# sparkpunk_sequencer.net
KiCad netlist of a schematic drawn in EAGLE
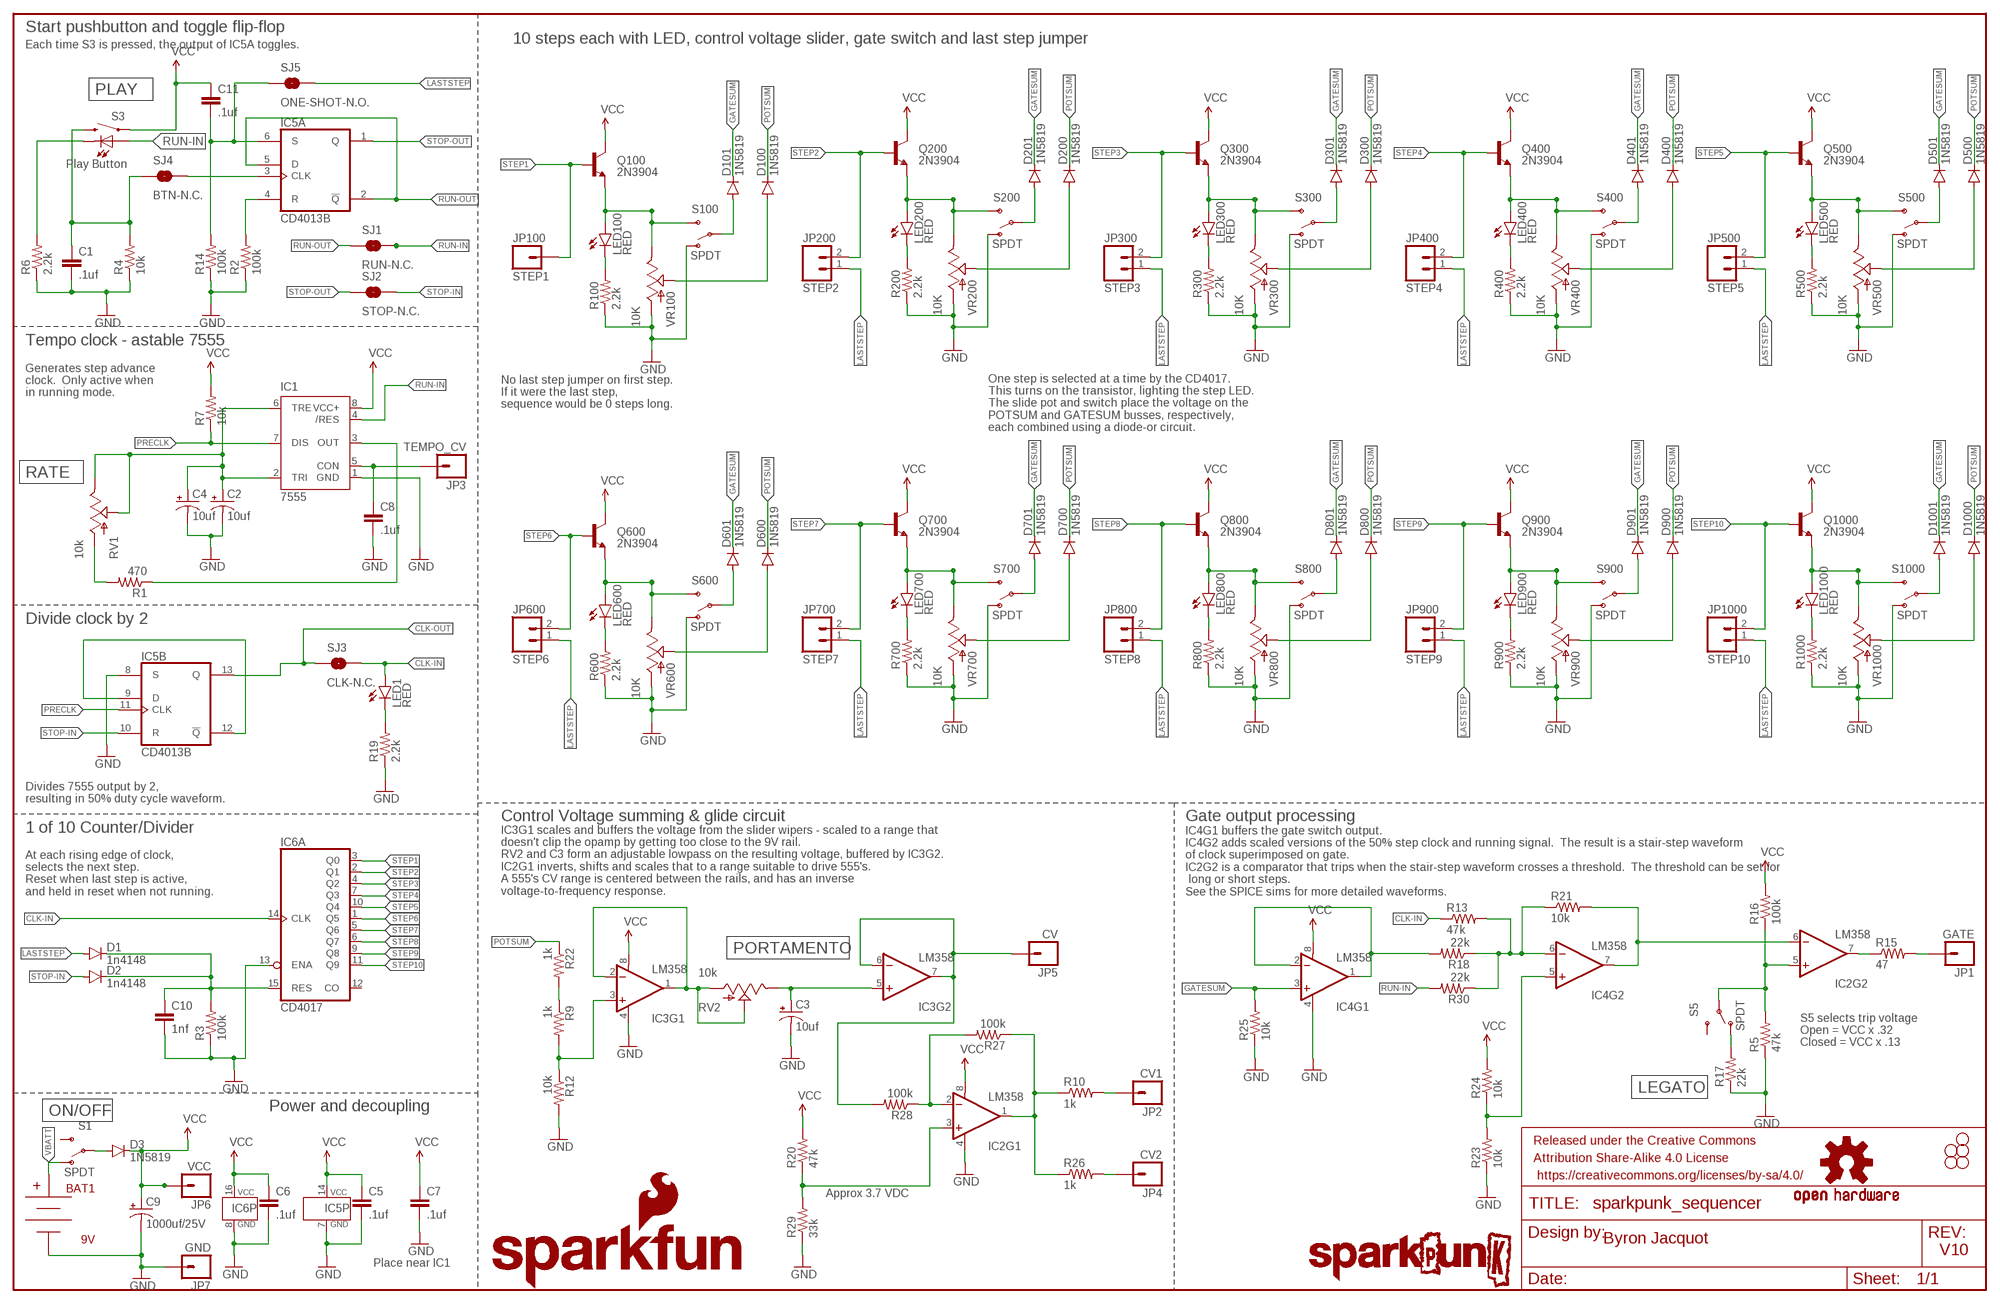
[diagram p0: schematic, sheet 1]

(export (version "E")
  (design (tool "Eeschema 10.0.6"))
  (components
    (comp (ref "BAT1")
      (value "9V")
      (footprint "eagle-import:BC9VPC_KIT")
      (libsource (lib "eagle-import") (part "BC9VPCKIT_SOLDERMASK"))
    )
    (comp (ref "C1")
      (value ".1uf")
      (footprint "eagle-import:CAP-PTH-SMALL-KIT")
      (libsource (lib "eagle-import") (part "0.1UF-50V-20%(PTH)KIT-EZ"))
    )
    (comp (ref "C2")
      (value "10uf")
      (footprint "eagle-import:CPOL-RADIAL-10UF-25V-KIT")
      (libsource (lib "eagle-import") (part "10UF-25V-20%(PTH)KIT"))
    )
    (comp (ref "C3")
      (value "10uf")
      (footprint "eagle-import:CPOL-RADIAL-10UF-25V-KIT")
      (libsource (lib "eagle-import") (part "10UF-25V-20%(PTH)KIT"))
    )
    (comp (ref "C4")
      (value "10uf")
      (footprint "eagle-import:CPOL-RADIAL-10UF-25V-KIT")
      (libsource (lib "eagle-import") (part "10UF-25V-20%(PTH)KIT"))
    )
    (comp (ref "C5")
      (value ".1uf")
      (footprint "eagle-import:CAP-PTH-SMALL-KIT")
      (libsource (lib "eagle-import") (part "0.1UF-50V-20%(PTH)KIT-EZ"))
    )
    (comp (ref "C6")
      (value ".1uf")
      (footprint "eagle-import:CAP-PTH-SMALL-KIT")
      (libsource (lib "eagle-import") (part "0.1UF-50V-20%(PTH)KIT-EZ"))
    )
    (comp (ref "C7")
      (value ".1uf")
      (footprint "eagle-import:CAP-PTH-SMALL-KIT")
      (libsource (lib "eagle-import") (part "0.1UF-50V-20%(PTH)KIT-EZ"))
    )
    (comp (ref "C8")
      (value ".1uf")
      (footprint "eagle-import:CAP-PTH-SMALL-KIT")
      (libsource (lib "eagle-import") (part "0.1UF-50V-20%(PTH)KIT-EZ"))
    )
    (comp (ref "C9")
      (value "1000uf/25V")
      (footprint "eagle-import:CPOL-RADIAL-1000UF-25V-KIT")
      (libsource (lib "eagle-import") (part "1000UF-25V(PTH)KIT"))
    )
    (comp (ref "C10")
      (value "1nf")
      (footprint "eagle-import:CAP-PTH-SMALL-KIT")
      (libsource (lib "eagle-import") (part "CAPKIT"))
    )
    (comp (ref "C11")
      (value ".1uf")
      (footprint "eagle-import:CAP-PTH-SMALL-KIT")
      (libsource (lib "eagle-import") (part "0.1UF-50V-20%(PTH)KIT-EZ"))
    )
    (comp (ref "D1")
      (value "1n4148")
      (footprint "eagle-import:DIODE-1N4148-KIT")
      (libsource (lib "eagle-import") (part "DIODEKIT"))
    )
    (comp (ref "D2")
      (value "1n4148")
      (footprint "eagle-import:DIODE-1N4148-KIT")
      (libsource (lib "eagle-import") (part "DIODEKIT"))
    )
    (comp (ref "D3")
      (value "1N5819")
      (footprint "eagle-import:DIODE-1N4001-KIT")
      (libsource (lib "eagle-import") (part "DIODE"))
    )
    (comp (ref "D100")
      (value "1N5819")
      (footprint "eagle-import:DIODE-1N4001-KIT")
      (libsource (lib "eagle-import") (part "DIODE"))
    )
    (comp (ref "D101")
      (value "1N5819")
      (footprint "eagle-import:DIODE-1N4001-KIT")
      (libsource (lib "eagle-import") (part "DIODE"))
    )
    (comp (ref "D200")
      (value "1N5819")
      (footprint "eagle-import:DIODE-1N4001-KIT")
      (libsource (lib "eagle-import") (part "DIODE"))
    )
    (comp (ref "D201")
      (value "1N5819")
      (footprint "eagle-import:DIODE-1N4001-KIT")
      (libsource (lib "eagle-import") (part "DIODE"))
    )
    (comp (ref "D300")
      (value "1N5819")
      (footprint "eagle-import:DIODE-1N4001-KIT")
      (libsource (lib "eagle-import") (part "DIODE"))
    )
    (comp (ref "D301")
      (value "1N5819")
      (footprint "eagle-import:DIODE-1N4001-KIT")
      (libsource (lib "eagle-import") (part "DIODE"))
    )
    (comp (ref "D400")
      (value "1N5819")
      (footprint "eagle-import:DIODE-1N4001-KIT")
      (libsource (lib "eagle-import") (part "DIODE"))
    )
    (comp (ref "D401")
      (value "1N5819")
      (footprint "eagle-import:DIODE-1N4001-KIT")
      (libsource (lib "eagle-import") (part "DIODE"))
    )
    (comp (ref "D500")
      (value "1N5819")
      (footprint "eagle-import:DIODE-1N4001-KIT")
      (libsource (lib "eagle-import") (part "DIODE"))
    )
    (comp (ref "D501")
      (value "1N5819")
      (footprint "eagle-import:DIODE-1N4001-KIT")
      (libsource (lib "eagle-import") (part "DIODE"))
    )
    (comp (ref "D600")
      (value "1N5819")
      (footprint "eagle-import:DIODE-1N4001-KIT")
      (libsource (lib "eagle-import") (part "DIODE"))
    )
    (comp (ref "D601")
      (value "1N5819")
      (footprint "eagle-import:DIODE-1N4001-KIT")
      (libsource (lib "eagle-import") (part "DIODE"))
    )
    (comp (ref "D700")
      (value "1N5819")
      (footprint "eagle-import:DIODE-1N4001-KIT")
      (libsource (lib "eagle-import") (part "DIODE"))
    )
    (comp (ref "D701")
      (value "1N5819")
      (footprint "eagle-import:DIODE-1N4001-KIT")
      (libsource (lib "eagle-import") (part "DIODE"))
    )
    (comp (ref "D800")
      (value "1N5819")
      (footprint "eagle-import:DIODE-1N4001-KIT")
      (libsource (lib "eagle-import") (part "DIODE"))
    )
    (comp (ref "D801")
      (value "1N5819")
      (footprint "eagle-import:DIODE-1N4001-KIT")
      (libsource (lib "eagle-import") (part "DIODE"))
    )
    (comp (ref "D900")
      (value "1N5819")
      (footprint "eagle-import:DIODE-1N4001-KIT")
      (libsource (lib "eagle-import") (part "DIODE"))
    )
    (comp (ref "D901")
      (value "1N5819")
      (footprint "eagle-import:DIODE-1N4001-KIT")
      (libsource (lib "eagle-import") (part "DIODE"))
    )
    (comp (ref "D1000")
      (value "1N5819")
      (footprint "eagle-import:DIODE-1N4001-KIT")
      (libsource (lib "eagle-import") (part "DIODE"))
    )
    (comp (ref "D1001")
      (value "1N5819")
      (footprint "eagle-import:DIODE-1N4001-KIT")
      (libsource (lib "eagle-import") (part "DIODE"))
    )
    (comp (ref "FRAME1")
      (value "FRAME-LEDGER")
      (footprint "eagle-import:CREATIVE_COMMONS")
      (libsource (lib "eagle-import") (part "FRAME-LEDGER"))
    )
    (comp (ref "IC1")
      (value "7555")
      (footprint "eagle-import:DIP08-KIT")
      (libsource (lib "eagle-import") (part "NE555KIT"))
    )
    (comp (ref "IC2")
      (value "LM358")
      (footprint "eagle-import:DIP08-KIT")
      (libsource (lib "eagle-import") (part "LM358KIT"))
    )
    (comp (ref "IC3")
      (value "LM358")
      (footprint "eagle-import:DIP08-KIT")
      (libsource (lib "eagle-import") (part "LM358KIT"))
    )
    (comp (ref "IC4")
      (value "LM358")
      (footprint "eagle-import:DIP08-KIT")
      (libsource (lib "eagle-import") (part "LM358KIT"))
    )
    (comp (ref "IC5")
      (value "CD4013B")
      (footprint "eagle-import:DIL14-KIT")
      (fields (field (name "PROD_ID") "IC-11930"))
      (libsource (lib "eagle-import") (part "CD4013"))
    )
    (comp (ref "IC6")
      (value "CD4017")
      (footprint "eagle-import:DIL16-KIT")
      (fields (field (name "DIST") "Digikey") (field (name "DIST_ID") "296-2037-5-ND"))
      (libsource (lib "eagle-import") (part "CD4017KIT"))
    )
    (comp (ref "JP1")
      (value "GATE")
      (footprint "eagle-import:1X01NS")
      (libsource (lib "eagle-import") (part "M01SMDNS"))
    )
    (comp (ref "JP2")
      (value "CV1")
      (footprint "eagle-import:1X01NS")
      (libsource (lib "eagle-import") (part "M01SMDNS"))
    )
    (comp (ref "JP3")
      (value "TEMPO_CV")
      (footprint "eagle-import:1X01NS")
      (libsource (lib "eagle-import") (part "M01SMDNS"))
    )
    (comp (ref "JP4")
      (value "CV2")
      (footprint "eagle-import:1X01NS")
      (libsource (lib "eagle-import") (part "M01SMDNS"))
    )
    (comp (ref "JP5")
      (value "CV")
      (footprint "eagle-import:1X01NS")
      (libsource (lib "eagle-import") (part "M01SMDNS"))
    )
    (comp (ref "JP6")
      (value "VCC")
      (footprint "eagle-import:1X01NS")
      (libsource (lib "eagle-import") (part "M01SMDNS"))
    )
    (comp (ref "JP7")
      (value "GND")
      (footprint "eagle-import:1X01NS")
      (libsource (lib "eagle-import") (part "M01SMDNS"))
    )
    (comp (ref "JP100")
      (value "STEP1")
      (footprint "eagle-import:1X01NS")
      (libsource (lib "eagle-import") (part "M01SMDNS"))
    )
    (comp (ref "JP200")
      (value "STEP2")
      (footprint "eagle-import:1X02_NO_SILK")
      (libsource (lib "eagle-import") (part "M021X02_NO_SILK"))
    )
    (comp (ref "JP300")
      (value "STEP3")
      (footprint "eagle-import:1X02_NO_SILK")
      (libsource (lib "eagle-import") (part "M021X02_NO_SILK"))
    )
    (comp (ref "JP400")
      (value "STEP4")
      (footprint "eagle-import:1X02_NO_SILK")
      (libsource (lib "eagle-import") (part "M021X02_NO_SILK"))
    )
    (comp (ref "JP500")
      (value "STEP5")
      (footprint "eagle-import:1X02_NO_SILK")
      (libsource (lib "eagle-import") (part "M021X02_NO_SILK"))
    )
    (comp (ref "JP600")
      (value "STEP6")
      (footprint "eagle-import:1X02_NO_SILK")
      (libsource (lib "eagle-import") (part "M021X02_NO_SILK"))
    )
    (comp (ref "JP700")
      (value "STEP7")
      (footprint "eagle-import:1X02_NO_SILK")
      (libsource (lib "eagle-import") (part "M021X02_NO_SILK"))
    )
    (comp (ref "JP800")
      (value "STEP8")
      (footprint "eagle-import:1X02_NO_SILK")
      (libsource (lib "eagle-import") (part "M021X02_NO_SILK"))
    )
    (comp (ref "JP900")
      (value "STEP9")
      (footprint "eagle-import:1X02_NO_SILK")
      (libsource (lib "eagle-import") (part "M021X02_NO_SILK"))
    )
    (comp (ref "JP1000")
      (value "STEP10")
      (footprint "eagle-import:1X02_NO_SILK")
      (libsource (lib "eagle-import") (part "M021X02_NO_SILK"))
    )
    (comp (ref "LED1")
      (value "RED")
      (footprint "eagle-import:LED5MM-KIT")
      (libsource (lib "eagle-import") (part "LED5MM-KIT"))
    )
    (comp (ref "LED100")
      (value "RED")
      (footprint "eagle-import:LED5MM-KIT")
      (libsource (lib "eagle-import") (part "LED5MM-KIT"))
    )
    (comp (ref "LED200")
      (value "RED")
      (footprint "eagle-import:LED5MM-KIT")
      (libsource (lib "eagle-import") (part "LED5MM-KIT"))
    )
    (comp (ref "LED300")
      (value "RED")
      (footprint "eagle-import:LED5MM-KIT")
      (libsource (lib "eagle-import") (part "LED5MM-KIT"))
    )
    (comp (ref "LED400")
      (value "RED")
      (footprint "eagle-import:LED5MM-KIT")
      (libsource (lib "eagle-import") (part "LED5MM-KIT"))
    )
    (comp (ref "LED500")
      (value "RED")
      (footprint "eagle-import:LED5MM-KIT")
      (libsource (lib "eagle-import") (part "LED5MM-KIT"))
    )
    (comp (ref "LED600")
      (value "RED")
      (footprint "eagle-import:LED5MM-KIT")
      (libsource (lib "eagle-import") (part "LED5MM-KIT"))
    )
    (comp (ref "LED700")
      (value "RED")
      (footprint "eagle-import:LED5MM-KIT")
      (libsource (lib "eagle-import") (part "LED5MM-KIT"))
    )
    (comp (ref "LED800")
      (value "RED")
      (footprint "eagle-import:LED5MM-KIT")
      (libsource (lib "eagle-import") (part "LED5MM-KIT"))
    )
    (comp (ref "LED900")
      (value "RED")
      (footprint "eagle-import:LED5MM-KIT")
      (libsource (lib "eagle-import") (part "LED5MM-KIT"))
    )
    (comp (ref "LED1000")
      (value "RED")
      (footprint "eagle-import:LED5MM-KIT")
      (libsource (lib "eagle-import") (part "LED5MM-KIT"))
    )
    (comp (ref "LOGO1")
      (value "SPARKPUNK_LOGO.2_INCH_TALL")
      (footprint "eagle-import:SPARKPUNK_LOGO_.2")
      (libsource (lib "eagle-import") (part "SPARKPUNK_LOGO.2_INCH_TALL"))
    )
    (comp (ref "LOGO2")
      (value "OSHW-LOGOM")
      (footprint "eagle-import:OSHW-LOGO-M")
      (libsource (lib "eagle-import") (part "OSHW-LOGOM"))
    )
    (comp (ref "LOGO3")
      (value "SPARKPUNK_LOGO.1INCH_TALL")
      (footprint "eagle-import:SPARKPUNK_LOGO_.1")
      (libsource (lib "eagle-import") (part "SPARKPUNK_LOGO.1INCH_TALL"))
    )
    (comp (ref "LOGO4")
      (value "SFE_LOGO_NAME_FLAME.4_INCH")
      (footprint "eagle-import:SFE_LOGO_NAME_FLAME_.4")
      (libsource (lib "eagle-import") (part "SFE_LOGO_NAME_FLAME.4_INCH"))
    )
    (comp (ref "Q100")
      (value "2N3904")
      (footprint "eagle-import:TO-92-AMMO")
      (libsource (lib "eagle-import") (part "TRANSISTOR_NPNTO-92-AMMO"))
    )
    (comp (ref "Q200")
      (value "2N3904")
      (footprint "eagle-import:TO-92-AMMO")
      (libsource (lib "eagle-import") (part "TRANSISTOR_NPNTO-92-AMMO"))
    )
    (comp (ref "Q300")
      (value "2N3904")
      (footprint "eagle-import:TO-92-AMMO")
      (libsource (lib "eagle-import") (part "TRANSISTOR_NPNTO-92-AMMO"))
    )
    (comp (ref "Q400")
      (value "2N3904")
      (footprint "eagle-import:TO-92-AMMO")
      (libsource (lib "eagle-import") (part "TRANSISTOR_NPNTO-92-AMMO"))
    )
    (comp (ref "Q500")
      (value "2N3904")
      (footprint "eagle-import:TO-92-AMMO")
      (libsource (lib "eagle-import") (part "TRANSISTOR_NPNTO-92-AMMO"))
    )
    (comp (ref "Q600")
      (value "2N3904")
      (footprint "eagle-import:TO-92-AMMO")
      (libsource (lib "eagle-import") (part "TRANSISTOR_NPNTO-92-AMMO"))
    )
    (comp (ref "Q700")
      (value "2N3904")
      (footprint "eagle-import:TO-92-AMMO")
      (libsource (lib "eagle-import") (part "TRANSISTOR_NPNTO-92-AMMO"))
    )
    (comp (ref "Q800")
      (value "2N3904")
      (footprint "eagle-import:TO-92-AMMO")
      (libsource (lib "eagle-import") (part "TRANSISTOR_NPNTO-92-AMMO"))
    )
    (comp (ref "Q900")
      (value "2N3904")
      (footprint "eagle-import:TO-92-AMMO")
      (libsource (lib "eagle-import") (part "TRANSISTOR_NPNTO-92-AMMO"))
    )
    (comp (ref "Q1000")
      (value "2N3904")
      (footprint "eagle-import:TO-92-AMMO")
      (libsource (lib "eagle-import") (part "TRANSISTOR_NPNTO-92-AMMO"))
    )
    (comp (ref "R1")
      (value "470")
      (footprint "eagle-import:AXIAL-0.3EZ")
      (libsource (lib "eagle-import") (part "RESISTOREZ"))
    )
    (comp (ref "R2")
      (value "100k")
      (footprint "eagle-import:AXIAL-0.3EZ")
      (libsource (lib "eagle-import") (part "RESISTOREZ"))
    )
    (comp (ref "R3")
      (value "100k")
      (footprint "eagle-import:AXIAL-0.3EZ")
      (libsource (lib "eagle-import") (part "RESISTOREZ"))
    )
    (comp (ref "R4")
      (value "10k")
      (footprint "eagle-import:AXIAL-0.3EZ")
      (libsource (lib "eagle-import") (part "RESISTOREZ"))
    )
    (comp (ref "R5")
      (value "47k")
      (footprint "eagle-import:AXIAL-0.3EZ")
      (libsource (lib "eagle-import") (part "RESISTOREZ"))
    )
    (comp (ref "R6")
      (value "2.2k")
      (footprint "eagle-import:AXIAL-0.3EZ")
      (libsource (lib "eagle-import") (part "RESISTOREZ"))
    )
    (comp (ref "R7")
      (value "10k")
      (footprint "eagle-import:AXIAL-0.3EZ")
      (libsource (lib "eagle-import") (part "RESISTOREZ"))
    )
    (comp (ref "R9")
      (value "1k")
      (footprint "eagle-import:AXIAL-0.3EZ")
      (libsource (lib "eagle-import") (part "RESISTOREZ"))
    )
    (comp (ref "R10")
      (value "1k")
      (footprint "eagle-import:AXIAL-0.3EZ")
      (libsource (lib "eagle-import") (part "RESISTOREZ"))
    )
    (comp (ref "R12")
      (value "10k")
      (footprint "eagle-import:AXIAL-0.3EZ")
      (libsource (lib "eagle-import") (part "RESISTOREZ"))
    )
    (comp (ref "R13")
      (value "47k")
      (footprint "eagle-import:AXIAL-0.3EZ")
      (libsource (lib "eagle-import") (part "RESISTOREZ"))
    )
    (comp (ref "R14")
      (value "100k")
      (footprint "eagle-import:AXIAL-0.3EZ")
      (libsource (lib "eagle-import") (part "RESISTOREZ"))
    )
    (comp (ref "R15")
      (value "47")
      (footprint "eagle-import:AXIAL-0.3EZ")
      (libsource (lib "eagle-import") (part "RESISTOREZ"))
    )
    (comp (ref "R16")
      (value "100k")
      (footprint "eagle-import:AXIAL-0.3EZ")
      (libsource (lib "eagle-import") (part "RESISTOREZ"))
    )
    (comp (ref "R17")
      (value "22k")
      (footprint "eagle-import:AXIAL-0.3EZ")
      (libsource (lib "eagle-import") (part "RESISTOREZ"))
    )
    (comp (ref "R18")
      (value "22k")
      (footprint "eagle-import:AXIAL-0.3EZ")
      (libsource (lib "eagle-import") (part "RESISTOREZ"))
    )
    (comp (ref "R19")
      (value "2.2k")
      (footprint "eagle-import:AXIAL-0.3EZ")
      (libsource (lib "eagle-import") (part "RESISTOREZ"))
    )
    (comp (ref "R20")
      (value "47k")
      (footprint "eagle-import:AXIAL-0.3EZ")
      (libsource (lib "eagle-import") (part "RESISTOREZ"))
    )
    (comp (ref "R21")
      (value "10k")
      (footprint "eagle-import:AXIAL-0.3EZ")
      (libsource (lib "eagle-import") (part "RESISTOREZ"))
    )
    (comp (ref "R22")
      (value "1k")
      (footprint "eagle-import:AXIAL-0.3EZ")
      (libsource (lib "eagle-import") (part "RESISTOREZ"))
    )
    (comp (ref "R23")
      (value "10k")
      (footprint "eagle-import:AXIAL-0.3EZ")
      (libsource (lib "eagle-import") (part "RESISTOREZ"))
    )
    (comp (ref "R24")
      (value "10k")
      (footprint "eagle-import:AXIAL-0.3EZ")
      (libsource (lib "eagle-import") (part "RESISTOREZ"))
    )
    (comp (ref "R25")
      (value "10k")
      (footprint "eagle-import:AXIAL-0.3EZ")
      (libsource (lib "eagle-import") (part "RESISTOREZ"))
    )
    (comp (ref "R26")
      (value "1k")
      (footprint "eagle-import:AXIAL-0.3EZ")
      (libsource (lib "eagle-import") (part "RESISTOREZ"))
    )
    (comp (ref "R27")
      (value "100k")
      (footprint "eagle-import:AXIAL-0.3EZ")
      (libsource (lib "eagle-import") (part "RESISTOREZ"))
    )
    (comp (ref "R28")
      (value "100k")
      (footprint "eagle-import:AXIAL-0.3EZ")
      (libsource (lib "eagle-import") (part "RESISTOREZ"))
    )
    (comp (ref "R29")
      (value "33k")
      (footprint "eagle-import:AXIAL-0.3EZ")
      (libsource (lib "eagle-import") (part "RESISTOREZ"))
    )
    (comp (ref "R30")
      (value "22k")
      (footprint "eagle-import:AXIAL-0.3EZ")
      (libsource (lib "eagle-import") (part "RESISTOREZ"))
    )
    (comp (ref "R100")
      (value "2.2k")
      (footprint "eagle-import:AXIAL-0.3EZ")
      (libsource (lib "eagle-import") (part "RESISTOREZ"))
    )
    (comp (ref "R200")
      (value "2.2k")
      (footprint "eagle-import:AXIAL-0.3EZ")
      (libsource (lib "eagle-import") (part "RESISTOREZ"))
    )
    (comp (ref "R300")
      (value "2.2k")
      (footprint "eagle-import:AXIAL-0.3EZ")
      (libsource (lib "eagle-import") (part "RESISTOREZ"))
    )
    (comp (ref "R400")
      (value "2.2k")
      (footprint "eagle-import:AXIAL-0.3EZ")
      (libsource (lib "eagle-import") (part "RESISTOREZ"))
    )
    (comp (ref "R500")
      (value "2.2k")
      (footprint "eagle-import:AXIAL-0.3EZ")
      (libsource (lib "eagle-import") (part "RESISTOREZ"))
    )
    (comp (ref "R600")
      (value "2.2k")
      (footprint "eagle-import:AXIAL-0.3EZ")
      (libsource (lib "eagle-import") (part "RESISTOREZ"))
    )
    (comp (ref "R700")
      (value "2.2k")
      (footprint "eagle-import:AXIAL-0.3EZ")
      (libsource (lib "eagle-import") (part "RESISTOREZ"))
    )
    (comp (ref "R800")
      (value "2.2k")
      (footprint "eagle-import:AXIAL-0.3EZ")
      (libsource (lib "eagle-import") (part "RESISTOREZ"))
    )
    (comp (ref "R900")
      (value "2.2k")
      (footprint "eagle-import:AXIAL-0.3EZ")
      (libsource (lib "eagle-import") (part "RESISTOREZ"))
    )
    (comp (ref "R1000")
      (value "2.2k")
      (footprint "eagle-import:AXIAL-0.3EZ")
      (libsource (lib "eagle-import") (part "RESISTOREZ"))
    )
    (comp (ref "RV1")
      (value "10k")
      (footprint "eagle-import:ALPS_POT_KIT")
      (libsource (lib "eagle-import") (part "POTALPS-KIT"))
    )
    (comp (ref "RV2")
      (value "10k")
      (footprint "eagle-import:ALPS_POT_KIT")
      (libsource (lib "eagle-import") (part "POTALPS-KIT"))
    )
    (comp (ref "S1")
      (value "SPDT")
      (footprint "eagle-import:SWITCH-SPDT_KIT")
      (libsource (lib "eagle-import") (part "SWITCH-SPDTKIT"))
    )
    (comp (ref "S3")
      (value "Play Button")
      (footprint "eagle-import:TACTILE-PTH-LED-12MM-EZ")
      (libsource (lib "eagle-import") (part "SWITCH-MOMENTARY-LEDEZ"))
    )
    (comp (ref "S5")
      (value "SPDT")
      (footprint "eagle-import:SWITCH-SPDT_KIT")
      (libsource (lib "eagle-import") (part "SWITCH-SPDTKIT"))
    )
    (comp (ref "S100")
      (value "SPDT")
      (footprint "eagle-import:SWITCH-SPDT_KIT")
      (libsource (lib "eagle-import") (part "SWITCH-SPDTKIT"))
    )
    (comp (ref "S200")
      (value "SPDT")
      (footprint "eagle-import:SWITCH-SPDT_KIT")
      (libsource (lib "eagle-import") (part "SWITCH-SPDTKIT"))
    )
    (comp (ref "S300")
      (value "SPDT")
      (footprint "eagle-import:SWITCH-SPDT_KIT")
      (libsource (lib "eagle-import") (part "SWITCH-SPDTKIT"))
    )
    (comp (ref "S400")
      (value "SPDT")
      (footprint "eagle-import:SWITCH-SPDT_KIT")
      (libsource (lib "eagle-import") (part "SWITCH-SPDTKIT"))
    )
    (comp (ref "S500")
      (value "SPDT")
      (footprint "eagle-import:SWITCH-SPDT_KIT")
      (libsource (lib "eagle-import") (part "SWITCH-SPDTKIT"))
    )
    (comp (ref "S600")
      (value "SPDT")
      (footprint "eagle-import:SWITCH-SPDT_KIT")
      (libsource (lib "eagle-import") (part "SWITCH-SPDTKIT"))
    )
    (comp (ref "S700")
      (value "SPDT")
      (footprint "eagle-import:SWITCH-SPDT_KIT")
      (libsource (lib "eagle-import") (part "SWITCH-SPDTKIT"))
    )
    (comp (ref "S800")
      (value "SPDT")
      (footprint "eagle-import:SWITCH-SPDT_KIT")
      (libsource (lib "eagle-import") (part "SWITCH-SPDTKIT"))
    )
    (comp (ref "S900")
      (value "SPDT")
      (footprint "eagle-import:SWITCH-SPDT_KIT")
      (libsource (lib "eagle-import") (part "SWITCH-SPDTKIT"))
    )
    (comp (ref "S1000")
      (value "SPDT")
      (footprint "eagle-import:SWITCH-SPDT_KIT")
      (libsource (lib "eagle-import") (part "SWITCH-SPDTKIT"))
    )
    (comp (ref "SJ1")
      (value "RUN-N.C.")
      (footprint "eagle-import:SJ_2S-TRACE-PTH")
      (libsource (lib "eagle-import") (part "SOLDERJUMPERTRACE-PTH"))
    )
    (comp (ref "SJ2")
      (value "STOP-N.C.")
      (footprint "eagle-import:SJ_2S-TRACE-PTH")
      (libsource (lib "eagle-import") (part "SOLDERJUMPERTRACE-PTH"))
    )
    (comp (ref "SJ3")
      (value "CLK-N.C.")
      (footprint "eagle-import:SJ_2S-TRACE-PTH")
      (libsource (lib "eagle-import") (part "SOLDERJUMPERTRACE-PTH"))
    )
    (comp (ref "SJ4")
      (value "BTN-N.C.")
      (footprint "eagle-import:SJ_2S-TRACE-PTH")
      (libsource (lib "eagle-import") (part "SOLDERJUMPERTRACE-PTH"))
    )
    (comp (ref "SJ5")
      (value "ONE-SHOT-N.O.")
      (footprint "eagle-import:SJ_2S-PTH")
      (libsource (lib "eagle-import") (part "SOLDERJUMPERPTH"))
    )
    (comp (ref "STANDOFF1")
      (value "STAND-OFF")
      (footprint "eagle-import:STAND-OFF")
      (libsource (lib "eagle-import") (part "STAND-OFF"))
    )
    (comp (ref "STANDOFF2")
      (value "STAND-OFF")
      (footprint "eagle-import:STAND-OFF")
      (libsource (lib "eagle-import") (part "STAND-OFF"))
    )
    (comp (ref "STANDOFF3")
      (value "STAND-OFF")
      (footprint "eagle-import:STAND-OFF")
      (libsource (lib "eagle-import") (part "STAND-OFF"))
    )
    (comp (ref "STANDOFF5")
      (value "STAND-OFF")
      (footprint "eagle-import:STAND-OFF")
      (libsource (lib "eagle-import") (part "STAND-OFF"))
    )
    (comp (ref "STANDOFF6")
      (value "STAND-OFF")
      (footprint "eagle-import:STAND-OFF")
      (libsource (lib "eagle-import") (part "STAND-OFF"))
    )
    (comp (ref "VR100")
      (value "10K")
      (footprint "eagle-import:SLIDER-MEDIUM-KIT")
      (libsource (lib "eagle-import") (part "SLIDER30MM-KIT"))
    )
    (comp (ref "VR200")
      (value "10K")
      (footprint "eagle-import:SLIDER-MEDIUM-KIT")
      (libsource (lib "eagle-import") (part "SLIDER30MM-KIT"))
    )
    (comp (ref "VR300")
      (value "10K")
      (footprint "eagle-import:SLIDER-MEDIUM-KIT")
      (libsource (lib "eagle-import") (part "SLIDER30MM-KIT"))
    )
    (comp (ref "VR400")
      (value "10K")
      (footprint "eagle-import:SLIDER-MEDIUM-KIT")
      (libsource (lib "eagle-import") (part "SLIDER30MM-KIT"))
    )
    (comp (ref "VR500")
      (value "10K")
      (footprint "eagle-import:SLIDER-MEDIUM-KIT")
      (libsource (lib "eagle-import") (part "SLIDER30MM-KIT"))
    )
    (comp (ref "VR600")
      (value "10K")
      (footprint "eagle-import:SLIDER-MEDIUM-KIT")
      (libsource (lib "eagle-import") (part "SLIDER30MM-KIT"))
    )
    (comp (ref "VR700")
      (value "10K")
      (footprint "eagle-import:SLIDER-MEDIUM-KIT")
      (libsource (lib "eagle-import") (part "SLIDER30MM-KIT"))
    )
    (comp (ref "VR800")
      (value "10K")
      (footprint "eagle-import:SLIDER-MEDIUM-KIT")
      (libsource (lib "eagle-import") (part "SLIDER30MM-KIT"))
    )
    (comp (ref "VR900")
      (value "10K")
      (footprint "eagle-import:SLIDER-MEDIUM-KIT")
      (libsource (lib "eagle-import") (part "SLIDER30MM-KIT"))
    )
    (comp (ref "VR1000")
      (value "10K")
      (footprint "eagle-import:SLIDER-MEDIUM-KIT")
      (libsource (lib "eagle-import") (part "SLIDER30MM-KIT"))
    )
  )
  (nets
    (net (code "1") (name "CLK-IN") (class "Default")
      (node (ref "IC6") (pin "14") (pinfunction "CLK_14") (pintype "input"))
      (node (ref "LED1") (pin "A") (pinfunction "A_A") (pintype "passive"))
      (node (ref "R13") (pin "P$1") (pinfunction "1_P$1") (pintype "passive"))
      (node (ref "SJ3") (pin "2") (pinfunction "2_2") (pintype "passive"))
    )
    (net (code "2") (name "CLK-OUT") (class "Default")
      (node (ref "IC5") (pin "13") (pinfunction "Q_13") (pintype "output"))
      (node (ref "SJ3") (pin "1") (pinfunction "1_1") (pintype "passive"))
    )
    (net (code "3") (name "GATESUM") (class "Default")
      (node (ref "D1001") (pin "C") (pinfunction "C_C") (pintype "passive"))
      (node (ref "D101") (pin "C") (pinfunction "C_C") (pintype "passive"))
      (node (ref "D201") (pin "C") (pinfunction "C_C") (pintype "passive"))
      (node (ref "D301") (pin "C") (pinfunction "C_C") (pintype "passive"))
      (node (ref "D401") (pin "C") (pinfunction "C_C") (pintype "passive"))
      (node (ref "D501") (pin "C") (pinfunction "C_C") (pintype "passive"))
      (node (ref "D601") (pin "C") (pinfunction "C_C") (pintype "passive"))
      (node (ref "D701") (pin "C") (pinfunction "C_C") (pintype "passive"))
      (node (ref "D801") (pin "C") (pinfunction "C_C") (pintype "passive"))
      (node (ref "D901") (pin "C") (pinfunction "C_C") (pintype "passive"))
      (node (ref "IC4") (pin "3") (pinfunction "+IN_3") (pintype "input"))
      (node (ref "R25") (pin "P$2") (pinfunction "2_P$2") (pintype "passive"))
    )
    (net (code "4") (name "GND") (class "Default")
      (node (ref "BAT1") (pin "V-") (pinfunction "V-_V-") (pintype "bidirectional"))
      (node (ref "C1") (pin "2") (pinfunction "2_2") (pintype "passive"))
      (node (ref "C10") (pin "2") (pinfunction "2_2") (pintype "passive"))
      (node (ref "C2") (pin "2") (pinfunction "-_2") (pintype "passive"))
      (node (ref "C3") (pin "2") (pinfunction "-_2") (pintype "passive"))
      (node (ref "C4") (pin "2") (pinfunction "-_2") (pintype "passive"))
      (node (ref "C5") (pin "2") (pinfunction "2_2") (pintype "passive"))
      (node (ref "C6") (pin "2") (pinfunction "2_2") (pintype "passive"))
      (node (ref "C7") (pin "2") (pinfunction "2_2") (pintype "passive"))
      (node (ref "C8") (pin "2") (pinfunction "2_2") (pintype "passive"))
      (node (ref "C9") (pin "-") (pinfunction "-_-") (pintype "passive"))
      (node (ref "IC1") (pin "1") (pinfunction "GND_1") (pintype "power_in"))
      (node (ref "IC2") (pin "4") (pinfunction "V-_4") (pintype "power_in"))
      (node (ref "IC3") (pin "4") (pinfunction "V-_4") (pintype "power_in"))
      (node (ref "IC4") (pin "4") (pinfunction "V-_4") (pintype "power_in"))
      (node (ref "IC5") (pin "7") (pinfunction "GND_7") (pintype "power_in"))
      (node (ref "IC5") (pin "8") (pinfunction "S_8") (pintype "input"))
      (node (ref "IC6") (pin "13") (pinfunction "ENA_13") (pintype "input"))
      (node (ref "IC6") (pin "8") (pinfunction "GND_8") (pintype "power_in"))
      (node (ref "JP7") (pin "1") (pinfunction "1_1") (pintype "passive"))
      (node (ref "R100") (pin "P$1") (pinfunction "1_P$1") (pintype "passive"))
      (node (ref "R1000") (pin "P$1") (pinfunction "1_P$1") (pintype "passive"))
      (node (ref "R12") (pin "P$2") (pinfunction "2_P$2") (pintype "passive"))
      (node (ref "R14") (pin "P$1") (pinfunction "1_P$1") (pintype "passive"))
      (node (ref "R17") (pin "P$1") (pinfunction "1_P$1") (pintype "passive"))
      (node (ref "R19") (pin "P$1") (pinfunction "1_P$1") (pintype "passive"))
      (node (ref "R2") (pin "P$1") (pinfunction "1_P$1") (pintype "passive"))
      (node (ref "R200") (pin "P$1") (pinfunction "1_P$1") (pintype "passive"))
      (node (ref "R23") (pin "P$1") (pinfunction "1_P$1") (pintype "passive"))
      (node (ref "R25") (pin "P$1") (pinfunction "1_P$1") (pintype "passive"))
      (node (ref "R29") (pin "P$1") (pinfunction "1_P$1") (pintype "passive"))
      (node (ref "R3") (pin "P$1") (pinfunction "1_P$1") (pintype "passive"))
      (node (ref "R300") (pin "P$1") (pinfunction "1_P$1") (pintype "passive"))
      (node (ref "R4") (pin "P$1") (pinfunction "1_P$1") (pintype "passive"))
      (node (ref "R400") (pin "P$1") (pinfunction "1_P$1") (pintype "passive"))
      (node (ref "R5") (pin "P$1") (pinfunction "1_P$1") (pintype "passive"))
      (node (ref "R500") (pin "P$1") (pinfunction "1_P$1") (pintype "passive"))
      (node (ref "R6") (pin "P$1") (pinfunction "1_P$1") (pintype "passive"))
      (node (ref "R600") (pin "P$1") (pinfunction "1_P$1") (pintype "passive"))
      (node (ref "R700") (pin "P$1") (pinfunction "1_P$1") (pintype "passive"))
      (node (ref "R800") (pin "P$1") (pinfunction "1_P$1") (pintype "passive"))
      (node (ref "R900") (pin "P$1") (pinfunction "1_P$1") (pintype "passive"))
      (node (ref "S100") (pin "1") (pinfunction "O_1") (pintype "passive"))
      (node (ref "S1000") (pin "1") (pinfunction "O_1") (pintype "passive"))
      (node (ref "S200") (pin "1") (pinfunction "O_1") (pintype "passive"))
      (node (ref "S300") (pin "1") (pinfunction "O_1") (pintype "passive"))
      (node (ref "S400") (pin "1") (pinfunction "O_1") (pintype "passive"))
      (node (ref "S500") (pin "1") (pinfunction "O_1") (pintype "passive"))
      (node (ref "S600") (pin "1") (pinfunction "O_1") (pintype "passive"))
      (node (ref "S700") (pin "1") (pinfunction "O_1") (pintype "passive"))
      (node (ref "S800") (pin "1") (pinfunction "O_1") (pintype "passive"))
      (node (ref "S900") (pin "1") (pinfunction "O_1") (pintype "passive"))
      (node (ref "VR100") (pin "BOTTOM") (pinfunction "A_BOTTOM") (pintype "passive"))
      (node (ref "VR1000") (pin "BOTTOM") (pinfunction "A_BOTTOM") (pintype "passive"))
      (node (ref "VR200") (pin "BOTTOM") (pinfunction "A_BOTTOM") (pintype "passive"))
      (node (ref "VR300") (pin "BOTTOM") (pinfunction "A_BOTTOM") (pintype "passive"))
      (node (ref "VR400") (pin "BOTTOM") (pinfunction "A_BOTTOM") (pintype "passive"))
      (node (ref "VR500") (pin "BOTTOM") (pinfunction "A_BOTTOM") (pintype "passive"))
      (node (ref "VR600") (pin "BOTTOM") (pinfunction "A_BOTTOM") (pintype "passive"))
      (node (ref "VR700") (pin "BOTTOM") (pinfunction "A_BOTTOM") (pintype "passive"))
      (node (ref "VR800") (pin "BOTTOM") (pinfunction "A_BOTTOM") (pintype "passive"))
      (node (ref "VR900") (pin "BOTTOM") (pinfunction "A_BOTTOM") (pintype "passive"))
    )
    (net (code "5") (name "LASTSTEP") (class "Default")
      (node (ref "D1") (pin "A") (pinfunction "A_A") (pintype "passive"))
      (node (ref "JP1000") (pin "1") (pinfunction "1_1") (pintype "passive"))
      (node (ref "JP200") (pin "1") (pinfunction "1_1") (pintype "passive"))
      (node (ref "JP300") (pin "1") (pinfunction "1_1") (pintype "passive"))
      (node (ref "JP400") (pin "1") (pinfunction "1_1") (pintype "passive"))
      (node (ref "JP500") (pin "1") (pinfunction "1_1") (pintype "passive"))
      (node (ref "JP600") (pin "1") (pinfunction "1_1") (pintype "passive"))
      (node (ref "JP700") (pin "1") (pinfunction "1_1") (pintype "passive"))
      (node (ref "JP800") (pin "1") (pinfunction "1_1") (pintype "passive"))
      (node (ref "JP900") (pin "1") (pinfunction "1_1") (pintype "passive"))
      (node (ref "SJ5") (pin "2") (pinfunction "2_2") (pintype "passive"))
    )
    (net (code "6") (name "Net-(C2-+)") (class "Default")
      (node (ref "C2") (pin "1") (pinfunction "+_1") (pintype "passive"))
      (node (ref "C4") (pin "1") (pinfunction "+_1") (pintype "passive"))
      (node (ref "IC1") (pin "2") (pinfunction "TRI_2") (pintype "input"))
      (node (ref "IC1") (pin "6") (pinfunction "TRE_6") (pintype "input"))
      (node (ref "RV1") (pin "P$1") (pinfunction "E_P$1") (pintype "passive"))
      (node (ref "RV1") (pin "P$2") (pinfunction "S_P$2") (pintype "passive"))
    )
    (net (code "7") (name "Net-(C3-+)") (class "Default")
      (node (ref "C3") (pin "1") (pinfunction "+_1") (pintype "passive"))
      (node (ref "IC3") (pin "5") (pinfunction "+IN_5") (pintype "input"))
      (node (ref "RV2") (pin "P$1") (pinfunction "E_P$1") (pintype "passive"))
    )
    (net (code "8") (name "Net-(IC1-CON)") (class "Default")
      (node (ref "C8") (pin "1") (pinfunction "1_1") (pintype "passive"))
      (node (ref "IC1") (pin "5") (pinfunction "CON_5") (pintype "input"))
      (node (ref "JP3") (pin "1") (pinfunction "1_1") (pintype "passive"))
    )
    (net (code "9") (name "Net-(IC1-OUT)") (class "Default")
      (node (ref "IC1") (pin "3") (pinfunction "OUT_3") (pintype "output"))
      (node (ref "R1") (pin "P$1") (pinfunction "1_P$1") (pintype "passive"))
    )
    (net (code "10") (name "Net-(IC2A-+IN)") (class "Default")
      (node (ref "IC2") (pin "3") (pinfunction "+IN_3") (pintype "input"))
      (node (ref "R20") (pin "P$1") (pinfunction "1_P$1") (pintype "passive"))
      (node (ref "R29") (pin "P$2") (pinfunction "2_P$2") (pintype "passive"))
    )
    (net (code "11") (name "Net-(IC2A--IN)") (class "Default")
      (node (ref "IC2") (pin "2") (pinfunction "-IN_2") (pintype "input"))
      (node (ref "R27") (pin "P$2") (pinfunction "2_P$2") (pintype "passive"))
      (node (ref "R28") (pin "P$1") (pinfunction "1_P$1") (pintype "passive"))
    )
    (net (code "12") (name "Net-(IC2A-OUT)") (class "Default")
      (node (ref "IC2") (pin "1") (pinfunction "OUT_1") (pintype "output"))
      (node (ref "R10") (pin "P$1") (pinfunction "1_P$1") (pintype "passive"))
      (node (ref "R26") (pin "P$1") (pinfunction "1_P$1") (pintype "passive"))
      (node (ref "R27") (pin "P$1") (pinfunction "1_P$1") (pintype "passive"))
    )
    (net (code "13") (name "Net-(IC2B-+IN)") (class "Default")
      (node (ref "IC2") (pin "5") (pinfunction "+IN_5") (pintype "input"))
      (node (ref "R16") (pin "P$1") (pinfunction "1_P$1") (pintype "passive"))
      (node (ref "R5") (pin "P$2") (pinfunction "2_P$2") (pintype "passive"))
      (node (ref "S5") (pin "2") (pinfunction "P_2") (pintype "passive"))
    )
    (net (code "14") (name "Net-(IC2B--IN)") (class "Default")
      (node (ref "IC2") (pin "6") (pinfunction "-IN_6") (pintype "input"))
      (node (ref "IC4") (pin "7") (pinfunction "OUT_7") (pintype "output"))
      (node (ref "R21") (pin "P$2") (pinfunction "2_P$2") (pintype "passive"))
    )
    (net (code "15") (name "Net-(IC2B-OUT)") (class "Default")
      (node (ref "IC2") (pin "7") (pinfunction "OUT_7") (pintype "output"))
      (node (ref "R15") (pin "P$1") (pinfunction "1_P$1") (pintype "passive"))
    )
    (net (code "16") (name "Net-(IC3A-+IN)") (class "Default")
      (node (ref "IC3") (pin "3") (pinfunction "+IN_3") (pintype "input"))
      (node (ref "R12") (pin "P$1") (pinfunction "1_P$1") (pintype "passive"))
      (node (ref "R9") (pin "P$2") (pinfunction "2_P$2") (pintype "passive"))
    )
    (net (code "17") (name "Net-(IC3A--IN)") (class "Default")
      (node (ref "IC3") (pin "1") (pinfunction "OUT_1") (pintype "output"))
      (node (ref "IC3") (pin "2") (pinfunction "-IN_2") (pintype "input"))
      (node (ref "RV2") (pin "P$2") (pinfunction "S_P$2") (pintype "passive"))
      (node (ref "RV2") (pin "P$3") (pinfunction "A_P$3") (pintype "passive"))
    )
    (net (code "18") (name "Net-(IC3B--IN)") (class "Default")
      (node (ref "IC3") (pin "6") (pinfunction "-IN_6") (pintype "input"))
      (node (ref "IC3") (pin "7") (pinfunction "OUT_7") (pintype "output"))
      (node (ref "JP5") (pin "1") (pinfunction "1_1") (pintype "passive"))
      (node (ref "R28") (pin "P$2") (pinfunction "2_P$2") (pintype "passive"))
    )
    (net (code "19") (name "Net-(IC4A--IN)") (class "Default")
      (node (ref "IC4") (pin "1") (pinfunction "OUT_1") (pintype "output"))
      (node (ref "IC4") (pin "2") (pinfunction "-IN_2") (pintype "input"))
      (node (ref "R18") (pin "P$2") (pinfunction "2_P$2") (pintype "passive"))
    )
    (net (code "20") (name "Net-(IC4B-+IN)") (class "Default")
      (node (ref "IC4") (pin "5") (pinfunction "+IN_5") (pintype "input"))
      (node (ref "R23") (pin "P$2") (pinfunction "2_P$2") (pintype "passive"))
      (node (ref "R24") (pin "P$1") (pinfunction "1_P$1") (pintype "passive"))
    )
    (net (code "21") (name "Net-(IC4B--IN)") (class "Default")
      (node (ref "IC4") (pin "6") (pinfunction "-IN_6") (pintype "input"))
      (node (ref "R13") (pin "P$2") (pinfunction "2_P$2") (pintype "passive"))
      (node (ref "R18") (pin "P$1") (pinfunction "1_P$1") (pintype "passive"))
      (node (ref "R21") (pin "P$1") (pinfunction "1_P$1") (pintype "passive"))
      (node (ref "R30") (pin "P$1") (pinfunction "1_P$1") (pintype "passive"))
    )
    (net (code "22") (name "Net-(IC5A-CLK)") (class "Default")
      (node (ref "IC5") (pin "3") (pinfunction "CLK_3") (pintype "input"))
      (node (ref "SJ4") (pin "2") (pinfunction "2_2") (pintype "passive"))
    )
    (net (code "23") (name "Net-(IC5A-R)") (class "Default")
      (node (ref "IC5") (pin "4") (pinfunction "R_4") (pintype "input"))
      (node (ref "R2") (pin "P$2") (pinfunction "2_P$2") (pintype "passive"))
    )
    (net (code "24") (name "Net-(IC5A-S)") (class "Default")
      (node (ref "C11") (pin "2") (pinfunction "2_2") (pintype "passive"))
      (node (ref "IC5") (pin "6") (pinfunction "S_6") (pintype "input"))
      (node (ref "R14") (pin "P$2") (pinfunction "2_P$2") (pintype "passive"))
      (node (ref "SJ5") (pin "1") (pinfunction "1_1") (pintype "passive"))
    )
    (net (code "25") (name "Net-(IC5B-D)") (class "Default")
      (node (ref "IC5") (pin "12") (pinfunction "~{Q}_12") (pintype "output"))
      (node (ref "IC5") (pin "9") (pinfunction "D_9") (pintype "input"))
    )
    (net (code "26") (name "Net-(IC6A-RES)") (class "Default")
      (node (ref "C10") (pin "1") (pinfunction "1_1") (pintype "passive"))
      (node (ref "D1") (pin "C") (pinfunction "C_C") (pintype "passive"))
      (node (ref "D2") (pin "C") (pinfunction "C_C") (pintype "passive"))
      (node (ref "IC6") (pin "15") (pinfunction "RES_15") (pintype "input"))
      (node (ref "R3") (pin "P$2") (pinfunction "2_P$2") (pintype "passive"))
    )
    (net (code "27") (name "Net-(LED1-C)") (class "Default")
      (node (ref "LED1") (pin "K") (pinfunction "C_K") (pintype "passive"))
      (node (ref "R19") (pin "P$2") (pinfunction "2_P$2") (pintype "passive"))
    )
    (net (code "28") (name "Net-(LED100-C)") (class "Default")
      (node (ref "LED100") (pin "K") (pinfunction "C_K") (pintype "passive"))
      (node (ref "R100") (pin "P$2") (pinfunction "2_P$2") (pintype "passive"))
    )
    (net (code "29") (name "Net-(LED200-C)") (class "Default")
      (node (ref "LED200") (pin "K") (pinfunction "C_K") (pintype "passive"))
      (node (ref "R200") (pin "P$2") (pinfunction "2_P$2") (pintype "passive"))
    )
    (net (code "30") (name "Net-(LED300-C)") (class "Default")
      (node (ref "LED300") (pin "K") (pinfunction "C_K") (pintype "passive"))
      (node (ref "R300") (pin "P$2") (pinfunction "2_P$2") (pintype "passive"))
    )
    (net (code "31") (name "Net-(LED400-C)") (class "Default")
      (node (ref "LED400") (pin "K") (pinfunction "C_K") (pintype "passive"))
      (node (ref "R400") (pin "P$2") (pinfunction "2_P$2") (pintype "passive"))
    )
    (net (code "32") (name "Net-(LED500-C)") (class "Default")
      (node (ref "LED500") (pin "K") (pinfunction "C_K") (pintype "passive"))
      (node (ref "R500") (pin "P$2") (pinfunction "2_P$2") (pintype "passive"))
    )
    (net (code "33") (name "Net-(LED600-C)") (class "Default")
      (node (ref "LED600") (pin "K") (pinfunction "C_K") (pintype "passive"))
      (node (ref "R600") (pin "P$2") (pinfunction "2_P$2") (pintype "passive"))
    )
    (net (code "34") (name "Net-(LED700-C)") (class "Default")
      (node (ref "LED700") (pin "K") (pinfunction "C_K") (pintype "passive"))
      (node (ref "R700") (pin "P$2") (pinfunction "2_P$2") (pintype "passive"))
    )
    (net (code "35") (name "Net-(LED800-C)") (class "Default")
      (node (ref "LED800") (pin "K") (pinfunction "C_K") (pintype "passive"))
      (node (ref "R800") (pin "P$2") (pinfunction "2_P$2") (pintype "passive"))
    )
    (net (code "36") (name "Net-(LED900-C)") (class "Default")
      (node (ref "LED900") (pin "K") (pinfunction "C_K") (pintype "passive"))
      (node (ref "R900") (pin "P$2") (pinfunction "2_P$2") (pintype "passive"))
    )
    (net (code "37") (name "Net-(LED1000-C)") (class "Default")
      (node (ref "LED1000") (pin "K") (pinfunction "C_K") (pintype "passive"))
      (node (ref "R1000") (pin "P$2") (pinfunction "2_P$2") (pintype "passive"))
    )
    (net (code "38") (name "Net-(Q100-E)") (class "Default")
      (node (ref "LED100") (pin "A") (pinfunction "A_A") (pintype "passive"))
      (node (ref "Q100") (pin "1") (pinfunction "E_1") (pintype "passive"))
      (node (ref "S100") (pin "3") (pinfunction "S_3") (pintype "passive"))
      (node (ref "VR100") (pin "TOP") (pinfunction "E_TOP") (pintype "passive"))
    )
    (net (code "39") (name "Net-(Q200-E)") (class "Default")
      (node (ref "LED200") (pin "A") (pinfunction "A_A") (pintype "passive"))
      (node (ref "Q200") (pin "1") (pinfunction "E_1") (pintype "passive"))
      (node (ref "S200") (pin "3") (pinfunction "S_3") (pintype "passive"))
      (node (ref "VR200") (pin "TOP") (pinfunction "E_TOP") (pintype "passive"))
    )
    (net (code "40") (name "Net-(Q300-E)") (class "Default")
      (node (ref "LED300") (pin "A") (pinfunction "A_A") (pintype "passive"))
      (node (ref "Q300") (pin "1") (pinfunction "E_1") (pintype "passive"))
      (node (ref "S300") (pin "3") (pinfunction "S_3") (pintype "passive"))
      (node (ref "VR300") (pin "TOP") (pinfunction "E_TOP") (pintype "passive"))
    )
    (net (code "41") (name "Net-(Q400-E)") (class "Default")
      (node (ref "LED400") (pin "A") (pinfunction "A_A") (pintype "passive"))
      (node (ref "Q400") (pin "1") (pinfunction "E_1") (pintype "passive"))
      (node (ref "S400") (pin "3") (pinfunction "S_3") (pintype "passive"))
      (node (ref "VR400") (pin "TOP") (pinfunction "E_TOP") (pintype "passive"))
    )
    (net (code "42") (name "Net-(Q500-E)") (class "Default")
      (node (ref "LED500") (pin "A") (pinfunction "A_A") (pintype "passive"))
      (node (ref "Q500") (pin "1") (pinfunction "E_1") (pintype "passive"))
      (node (ref "S500") (pin "3") (pinfunction "S_3") (pintype "passive"))
      (node (ref "VR500") (pin "TOP") (pinfunction "E_TOP") (pintype "passive"))
    )
    (net (code "43") (name "Net-(Q600-E)") (class "Default")
      (node (ref "LED600") (pin "A") (pinfunction "A_A") (pintype "passive"))
      (node (ref "Q600") (pin "1") (pinfunction "E_1") (pintype "passive"))
      (node (ref "S600") (pin "3") (pinfunction "S_3") (pintype "passive"))
      (node (ref "VR600") (pin "TOP") (pinfunction "E_TOP") (pintype "passive"))
    )
    (net (code "44") (name "Net-(Q700-E)") (class "Default")
      (node (ref "LED700") (pin "A") (pinfunction "A_A") (pintype "passive"))
      (node (ref "Q700") (pin "1") (pinfunction "E_1") (pintype "passive"))
      (node (ref "S700") (pin "3") (pinfunction "S_3") (pintype "passive"))
      (node (ref "VR700") (pin "TOP") (pinfunction "E_TOP") (pintype "passive"))
    )
    (net (code "45") (name "Net-(Q800-E)") (class "Default")
      (node (ref "LED800") (pin "A") (pinfunction "A_A") (pintype "passive"))
      (node (ref "Q800") (pin "1") (pinfunction "E_1") (pintype "passive"))
      (node (ref "S800") (pin "3") (pinfunction "S_3") (pintype "passive"))
      (node (ref "VR800") (pin "TOP") (pinfunction "E_TOP") (pintype "passive"))
    )
    (net (code "46") (name "Net-(Q900-E)") (class "Default")
      (node (ref "LED900") (pin "A") (pinfunction "A_A") (pintype "passive"))
      (node (ref "Q900") (pin "1") (pinfunction "E_1") (pintype "passive"))
      (node (ref "S900") (pin "3") (pinfunction "S_3") (pintype "passive"))
      (node (ref "VR900") (pin "TOP") (pinfunction "E_TOP") (pintype "passive"))
    )
    (net (code "47") (name "Net-(Q1000-E)") (class "Default")
      (node (ref "LED1000") (pin "A") (pinfunction "A_A") (pintype "passive"))
      (node (ref "Q1000") (pin "1") (pinfunction "E_1") (pintype "passive"))
      (node (ref "S1000") (pin "3") (pinfunction "S_3") (pintype "passive"))
      (node (ref "VR1000") (pin "TOP") (pinfunction "E_TOP") (pintype "passive"))
    )
    (net (code "48") (name "Net-(R1-2)") (class "Default")
      (node (ref "R1") (pin "P$2") (pinfunction "2_P$2") (pintype "passive"))
      (node (ref "RV1") (pin "P$3") (pinfunction "A_P$3") (pintype "passive"))
    )
    (net (code "49") (name "Net-(R4-2)") (class "Default")
      (node (ref "C1") (pin "1") (pinfunction "1_1") (pintype "passive"))
      (node (ref "R4") (pin "P$2") (pinfunction "2_P$2") (pintype "passive"))
      (node (ref "S3") (pin "2") (pinfunction "2_2") (pintype "passive"))
      (node (ref "SJ4") (pin "1") (pinfunction "1_1") (pintype "passive"))
    )
    (net (code "50") (name "Net-(R6-2)") (class "Default")
      (node (ref "R6") (pin "P$2") (pinfunction "2_P$2") (pintype "passive"))
      (node (ref "S3") (pin "C") (pinfunction "C_C") (pintype "passive"))
    )
    (net (code "51") (name "Net-(R10-2)") (class "Default")
      (node (ref "JP2") (pin "1") (pinfunction "1_1") (pintype "passive"))
      (node (ref "R10") (pin "P$2") (pinfunction "2_P$2") (pintype "passive"))
    )
    (net (code "52") (name "Net-(R15-2)") (class "Default")
      (node (ref "JP1") (pin "1") (pinfunction "1_1") (pintype "passive"))
      (node (ref "R15") (pin "P$2") (pinfunction "2_P$2") (pintype "passive"))
    )
    (net (code "53") (name "Net-(R17-2)") (class "Default")
      (node (ref "R17") (pin "P$2") (pinfunction "2_P$2") (pintype "passive"))
      (node (ref "S5") (pin "1") (pinfunction "O_1") (pintype "passive"))
    )
    (net (code "54") (name "Net-(R22-2)") (class "Default")
      (node (ref "R22") (pin "P$2") (pinfunction "2_P$2") (pintype "passive"))
      (node (ref "R9") (pin "P$1") (pinfunction "1_P$1") (pintype "passive"))
    )
    (net (code "55") (name "Net-(R26-2)") (class "Default")
      (node (ref "JP4") (pin "1") (pinfunction "1_1") (pintype "passive"))
      (node (ref "R26") (pin "P$2") (pinfunction "2_P$2") (pintype "passive"))
    )
    (net (code "56") (name "Net-(S1-P)") (class "Default")
      (node (ref "D3") (pin "A") (pinfunction "A_A") (pintype "passive"))
      (node (ref "S1") (pin "2") (pinfunction "P_2") (pintype "passive"))
    )
    (net (code "57") (name "Net-(S100-P)") (class "Default")
      (node (ref "D101") (pin "A") (pinfunction "A_A") (pintype "passive"))
      (node (ref "S100") (pin "2") (pinfunction "P_2") (pintype "passive"))
    )
    (net (code "58") (name "Net-(S200-P)") (class "Default")
      (node (ref "D201") (pin "A") (pinfunction "A_A") (pintype "passive"))
      (node (ref "S200") (pin "2") (pinfunction "P_2") (pintype "passive"))
    )
    (net (code "59") (name "Net-(S300-P)") (class "Default")
      (node (ref "D301") (pin "A") (pinfunction "A_A") (pintype "passive"))
      (node (ref "S300") (pin "2") (pinfunction "P_2") (pintype "passive"))
    )
    (net (code "60") (name "Net-(S400-P)") (class "Default")
      (node (ref "D401") (pin "A") (pinfunction "A_A") (pintype "passive"))
      (node (ref "S400") (pin "2") (pinfunction "P_2") (pintype "passive"))
    )
    (net (code "61") (name "Net-(S500-P)") (class "Default")
      (node (ref "D501") (pin "A") (pinfunction "A_A") (pintype "passive"))
      (node (ref "S500") (pin "2") (pinfunction "P_2") (pintype "passive"))
    )
    (net (code "62") (name "Net-(S600-P)") (class "Default")
      (node (ref "D601") (pin "A") (pinfunction "A_A") (pintype "passive"))
      (node (ref "S600") (pin "2") (pinfunction "P_2") (pintype "passive"))
    )
    (net (code "63") (name "Net-(S700-P)") (class "Default")
      (node (ref "D701") (pin "A") (pinfunction "A_A") (pintype "passive"))
      (node (ref "S700") (pin "2") (pinfunction "P_2") (pintype "passive"))
    )
    (net (code "64") (name "Net-(S800-P)") (class "Default")
      (node (ref "D801") (pin "A") (pinfunction "A_A") (pintype "passive"))
      (node (ref "S800") (pin "2") (pinfunction "P_2") (pintype "passive"))
    )
    (net (code "65") (name "Net-(S900-P)") (class "Default")
      (node (ref "D901") (pin "A") (pinfunction "A_A") (pintype "passive"))
      (node (ref "S900") (pin "2") (pinfunction "P_2") (pintype "passive"))
    )
    (net (code "66") (name "Net-(S1000-P)") (class "Default")
      (node (ref "D1001") (pin "A") (pinfunction "A_A") (pintype "passive"))
      (node (ref "S1000") (pin "2") (pinfunction "P_2") (pintype "passive"))
    )
    (net (code "67") (name "Net-(VR100-S)") (class "Default")
      (node (ref "D100") (pin "A") (pinfunction "A_A") (pintype "passive"))
      (node (ref "VR100") (pin "WIPER") (pinfunction "S_WIPER") (pintype "passive"))
    )
    (net (code "68") (name "Net-(VR200-S)") (class "Default")
      (node (ref "D200") (pin "A") (pinfunction "A_A") (pintype "passive"))
      (node (ref "VR200") (pin "WIPER") (pinfunction "S_WIPER") (pintype "passive"))
    )
    (net (code "69") (name "Net-(VR300-S)") (class "Default")
      (node (ref "D300") (pin "A") (pinfunction "A_A") (pintype "passive"))
      (node (ref "VR300") (pin "WIPER") (pinfunction "S_WIPER") (pintype "passive"))
    )
    (net (code "70") (name "Net-(VR400-S)") (class "Default")
      (node (ref "D400") (pin "A") (pinfunction "A_A") (pintype "passive"))
      (node (ref "VR400") (pin "WIPER") (pinfunction "S_WIPER") (pintype "passive"))
    )
    (net (code "71") (name "Net-(VR500-S)") (class "Default")
      (node (ref "D500") (pin "A") (pinfunction "A_A") (pintype "passive"))
      (node (ref "VR500") (pin "WIPER") (pinfunction "S_WIPER") (pintype "passive"))
    )
    (net (code "72") (name "Net-(VR600-S)") (class "Default")
      (node (ref "D600") (pin "A") (pinfunction "A_A") (pintype "passive"))
      (node (ref "VR600") (pin "WIPER") (pinfunction "S_WIPER") (pintype "passive"))
    )
    (net (code "73") (name "Net-(VR700-S)") (class "Default")
      (node (ref "D700") (pin "A") (pinfunction "A_A") (pintype "passive"))
      (node (ref "VR700") (pin "WIPER") (pinfunction "S_WIPER") (pintype "passive"))
    )
    (net (code "74") (name "Net-(VR800-S)") (class "Default")
      (node (ref "D800") (pin "A") (pinfunction "A_A") (pintype "passive"))
      (node (ref "VR800") (pin "WIPER") (pinfunction "S_WIPER") (pintype "passive"))
    )
    (net (code "75") (name "Net-(VR900-S)") (class "Default")
      (node (ref "D900") (pin "A") (pinfunction "A_A") (pintype "passive"))
      (node (ref "VR900") (pin "WIPER") (pinfunction "S_WIPER") (pintype "passive"))
    )
    (net (code "76") (name "Net-(VR1000-S)") (class "Default")
      (node (ref "D1000") (pin "A") (pinfunction "A_A") (pintype "passive"))
      (node (ref "VR1000") (pin "WIPER") (pinfunction "S_WIPER") (pintype "passive"))
    )
    (net (code "77") (name "POTSUM") (class "Default")
      (node (ref "D100") (pin "C") (pinfunction "C_C") (pintype "passive"))
      (node (ref "D1000") (pin "C") (pinfunction "C_C") (pintype "passive"))
      (node (ref "D200") (pin "C") (pinfunction "C_C") (pintype "passive"))
      (node (ref "D300") (pin "C") (pinfunction "C_C") (pintype "passive"))
      (node (ref "D400") (pin "C") (pinfunction "C_C") (pintype "passive"))
      (node (ref "D500") (pin "C") (pinfunction "C_C") (pintype "passive"))
      (node (ref "D600") (pin "C") (pinfunction "C_C") (pintype "passive"))
      (node (ref "D700") (pin "C") (pinfunction "C_C") (pintype "passive"))
      (node (ref "D800") (pin "C") (pinfunction "C_C") (pintype "passive"))
      (node (ref "D900") (pin "C") (pinfunction "C_C") (pintype "passive"))
      (node (ref "R22") (pin "P$1") (pinfunction "1_P$1") (pintype "passive"))
    )
    (net (code "78") (name "PRECLK") (class "Default")
      (node (ref "IC1") (pin "7") (pinfunction "DIS_7") (pintype "input"))
      (node (ref "IC5") (pin "11") (pinfunction "CLK_11") (pintype "input"))
      (node (ref "R7") (pin "P$1") (pinfunction "1_P$1") (pintype "passive"))
    )
    (net (code "79") (name "RUN-IN") (class "Default")
      (node (ref "IC1") (pin "4") (pinfunction "/RES_4") (pintype "input"))
      (node (ref "R30") (pin "P$2") (pinfunction "2_P$2") (pintype "passive"))
      (node (ref "S3") (pin "A") (pinfunction "A_A") (pintype "passive"))
      (node (ref "SJ1") (pin "2") (pinfunction "2_2") (pintype "passive"))
    )
    (net (code "80") (name "RUN-OUT") (class "Default")
      (node (ref "IC5") (pin "2") (pinfunction "~{Q}_2") (pintype "output"))
      (node (ref "IC5") (pin "5") (pinfunction "D_5") (pintype "input"))
      (node (ref "SJ1") (pin "1") (pinfunction "1_1") (pintype "passive"))
    )
    (net (code "81") (name "STEP1") (class "Default")
      (node (ref "IC6") (pin "3") (pinfunction "Q0_3") (pintype "output"))
      (node (ref "JP100") (pin "1") (pinfunction "1_1") (pintype "passive"))
      (node (ref "Q100") (pin "2") (pinfunction "B_2") (pintype "passive"))
    )
    (net (code "82") (name "STEP2") (class "Default")
      (node (ref "IC6") (pin "2") (pinfunction "Q1_2") (pintype "output"))
      (node (ref "JP200") (pin "2") (pinfunction "2_2") (pintype "passive"))
      (node (ref "Q200") (pin "2") (pinfunction "B_2") (pintype "passive"))
    )
    (net (code "83") (name "STEP3") (class "Default")
      (node (ref "IC6") (pin "4") (pinfunction "Q2_4") (pintype "output"))
      (node (ref "JP300") (pin "2") (pinfunction "2_2") (pintype "passive"))
      (node (ref "Q300") (pin "2") (pinfunction "B_2") (pintype "passive"))
    )
    (net (code "84") (name "STEP4") (class "Default")
      (node (ref "IC6") (pin "7") (pinfunction "Q3_7") (pintype "output"))
      (node (ref "JP400") (pin "2") (pinfunction "2_2") (pintype "passive"))
      (node (ref "Q400") (pin "2") (pinfunction "B_2") (pintype "passive"))
    )
    (net (code "85") (name "STEP5") (class "Default")
      (node (ref "IC6") (pin "10") (pinfunction "Q4_10") (pintype "output"))
      (node (ref "JP500") (pin "2") (pinfunction "2_2") (pintype "passive"))
      (node (ref "Q500") (pin "2") (pinfunction "B_2") (pintype "passive"))
    )
    (net (code "86") (name "STEP6") (class "Default")
      (node (ref "IC6") (pin "1") (pinfunction "Q5_1") (pintype "output"))
      (node (ref "JP600") (pin "2") (pinfunction "2_2") (pintype "passive"))
      (node (ref "Q600") (pin "2") (pinfunction "B_2") (pintype "passive"))
    )
    (net (code "87") (name "STEP7") (class "Default")
      (node (ref "IC6") (pin "5") (pinfunction "Q6_5") (pintype "output"))
      (node (ref "JP700") (pin "2") (pinfunction "2_2") (pintype "passive"))
      (node (ref "Q700") (pin "2") (pinfunction "B_2") (pintype "passive"))
    )
    (net (code "88") (name "STEP8") (class "Default")
      (node (ref "IC6") (pin "6") (pinfunction "Q7_6") (pintype "output"))
      (node (ref "JP800") (pin "2") (pinfunction "2_2") (pintype "passive"))
      (node (ref "Q800") (pin "2") (pinfunction "B_2") (pintype "passive"))
    )
    (net (code "89") (name "STEP9") (class "Default")
      (node (ref "IC6") (pin "9") (pinfunction "Q8_9") (pintype "output"))
      (node (ref "JP900") (pin "2") (pinfunction "2_2") (pintype "passive"))
      (node (ref "Q900") (pin "2") (pinfunction "B_2") (pintype "passive"))
    )
    (net (code "90") (name "STEP10") (class "Default")
      (node (ref "IC6") (pin "11") (pinfunction "Q9_11") (pintype "output"))
      (node (ref "JP1000") (pin "2") (pinfunction "2_2") (pintype "passive"))
      (node (ref "Q1000") (pin "2") (pinfunction "B_2") (pintype "passive"))
    )
    (net (code "91") (name "STOP-IN") (class "Default")
      (node (ref "D2") (pin "A") (pinfunction "A_A") (pintype "passive"))
      (node (ref "IC5") (pin "10") (pinfunction "R_10") (pintype "input"))
      (node (ref "SJ2") (pin "2") (pinfunction "2_2") (pintype "passive"))
    )
    (net (code "92") (name "STOP-OUT") (class "Default")
      (node (ref "IC5") (pin "1") (pinfunction "Q_1") (pintype "output"))
      (node (ref "SJ2") (pin "1") (pinfunction "1_1") (pintype "passive"))
    )
    (net (code "93") (name "VBATT") (class "Default")
      (node (ref "BAT1") (pin "V+") (pinfunction "V+_V+") (pintype "bidirectional"))
      (node (ref "S1") (pin "1") (pinfunction "O_1") (pintype "passive"))
    )
    (net (code "94") (name "VCC") (class "Default")
      (node (ref "C11") (pin "1") (pinfunction "1_1") (pintype "passive"))
      (node (ref "C5") (pin "1") (pinfunction "1_1") (pintype "passive"))
      (node (ref "C6") (pin "1") (pinfunction "1_1") (pintype "passive"))
      (node (ref "C7") (pin "1") (pinfunction "1_1") (pintype "passive"))
      (node (ref "C9") (pin "+") (pinfunction "+_+") (pintype "passive"))
      (node (ref "D3") (pin "C") (pinfunction "C_C") (pintype "passive"))
      (node (ref "IC1") (pin "8") (pinfunction "VCC+_8") (pintype "power_in"))
      (node (ref "IC2") (pin "8") (pinfunction "V+_8") (pintype "power_in"))
      (node (ref "IC3") (pin "8") (pinfunction "V+_8") (pintype "power_in"))
      (node (ref "IC4") (pin "8") (pinfunction "V+_8") (pintype "power_in"))
      (node (ref "IC5") (pin "14") (pinfunction "VCC_14") (pintype "power_in"))
      (node (ref "IC6") (pin "16") (pinfunction "VCC_16") (pintype "power_in"))
      (node (ref "JP6") (pin "1") (pinfunction "1_1") (pintype "passive"))
      (node (ref "Q100") (pin "3") (pinfunction "C_3") (pintype "passive"))
      (node (ref "Q1000") (pin "3") (pinfunction "C_3") (pintype "passive"))
      (node (ref "Q200") (pin "3") (pinfunction "C_3") (pintype "passive"))
      (node (ref "Q300") (pin "3") (pinfunction "C_3") (pintype "passive"))
      (node (ref "Q400") (pin "3") (pinfunction "C_3") (pintype "passive"))
      (node (ref "Q500") (pin "3") (pinfunction "C_3") (pintype "passive"))
      (node (ref "Q600") (pin "3") (pinfunction "C_3") (pintype "passive"))
      (node (ref "Q700") (pin "3") (pinfunction "C_3") (pintype "passive"))
      (node (ref "Q800") (pin "3") (pinfunction "C_3") (pintype "passive"))
      (node (ref "Q900") (pin "3") (pinfunction "C_3") (pintype "passive"))
      (node (ref "R16") (pin "P$2") (pinfunction "2_P$2") (pintype "passive"))
      (node (ref "R20") (pin "P$2") (pinfunction "2_P$2") (pintype "passive"))
      (node (ref "R24") (pin "P$2") (pinfunction "2_P$2") (pintype "passive"))
      (node (ref "R7") (pin "P$2") (pinfunction "2_P$2") (pintype "passive"))
      (node (ref "S3") (pin "4") (pinfunction "1_4") (pintype "passive"))
    )
    (net (code "95") (name "unconnected-(IC6A-CO-Pad12)") (class "Default")
      (node (ref "IC6") (pin "12") (pinfunction "CO_12") (pintype "output"))
    )
    (net (code "96") (name "unconnected-(S1-S-Pad3)") (class "Default")
      (node (ref "S1") (pin "3") (pinfunction "S_3") (pintype "passive"))
    )
    (net (code "97") (name "unconnected-(S5-S-Pad3)") (class "Default")
      (node (ref "S5") (pin "3") (pinfunction "S_3") (pintype "passive"))
    )
  )
)
